# guimoOpen_PCB.net
KiCad netlist of a schematic drawn in EAGLE
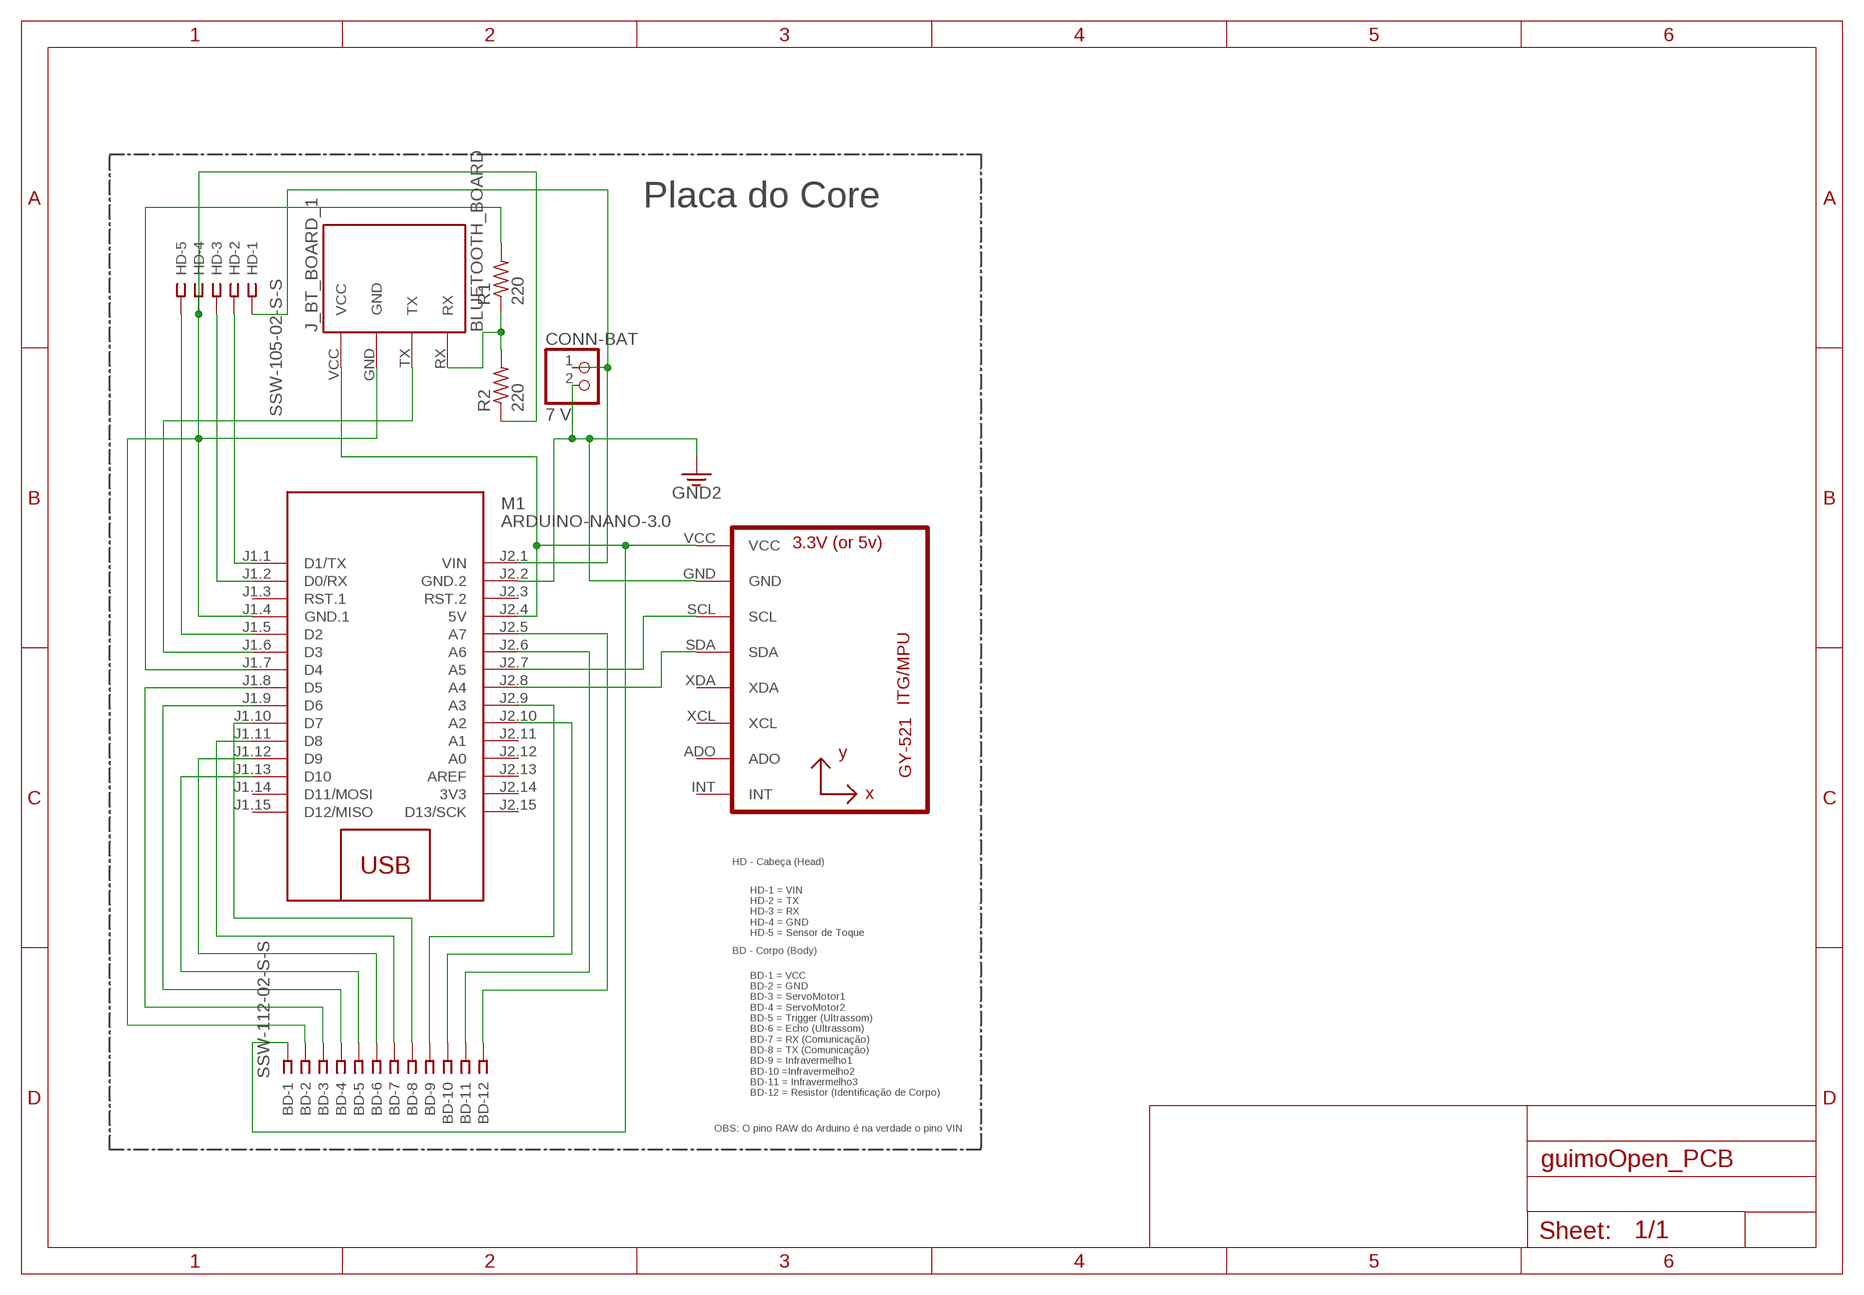
[diagram p0: schematic, sheet 1]

(export (version "E")
  (design (tool "Eeschema 10.0.6"))
  (components
    (comp (ref "BD")
      (value "SSW-112-02-S-S")
      (footprint "eagle-import:SSW-112-02-S-S")
      (libsource (lib "eagle-import") (part "SSW-112-02-S-S"))
    )
    (comp (ref "CONN-BAT")
      (value "7 V")
      (footprint "eagle-import:1X02")
      (libsource (lib "eagle-import") (part "PINHD-1X2"))
    )
    (comp (ref "HD")
      (value "SSW-105-02-S-S")
      (footprint "eagle-import:SSW-105-02-S-S")
      (libsource (lib "eagle-import") (part "SSW-105-02-S-S"))
    )
    (comp (ref "J_BT_BOARD_1")
      (value "BLUETOOTH_BOARD")
      (footprint "eagle-import:BT_BOARD_FOOTPRINT")
      (libsource (lib "eagle-import") (part "BLUETOOTH_BOARD"))
    )
    (comp (ref "M1")
      (value "ARDUINO-NANO-3.0")
      (footprint "eagle-import:ARDUINO-NANO-3.0")
      (libsource (lib "eagle-import") (part "ARDUINO-NANO-3.0"))
    )
    (comp (ref "R1")
      (value "220")
      (footprint "eagle-import:0207_7")
      (libsource (lib "eagle-import") (part "R-US_0207/7"))
    )
    (comp (ref "R2")
      (value "220")
      (footprint "eagle-import:0207_7")
      (libsource (lib "eagle-import") (part "R-US_0207/7"))
    )
    (comp (ref "U1")
      (value "GY-521MPU6050")
      (footprint "eagle-import:GY-521")
      (libsource (lib "eagle-import") (part "GY-521MPU6050"))
    )
  )
  (nets
    (net (code "1") (name "/3V3") (class "Default")
      (node (ref "M1") (pin "J2.14") (pinfunction "3V3_J2.14") (pintype "power_in"))
    )
    (net (code "2") (name "GND2") (class "Default")
      (node (ref "CONN-BAT") (pin "2") (pinfunction "2_2") (pintype "passive"))
      (node (ref "M1") (pin "J2.2") (pinfunction "GND.2_J2.2") (pintype "power_in"))
      (node (ref "U1") (pin "GND") (pinfunction "GND_GND") (pintype "bidirectional"))
    )
    (net (code "3") (name "Net-(BDB-1)") (class "Default")
      (node (ref "BD") (pin "10") (pinfunction "1_10") (pintype "passive"))
      (node (ref "M1") (pin "J2.10") (pinfunction "A2_J2.10") (pintype "bidirectional"))
    )
    (net (code "4") (name "Net-(BDC-1)") (class "Default")
      (node (ref "BD") (pin "11") (pinfunction "1_11") (pintype "passive"))
      (node (ref "M1") (pin "J2.6") (pinfunction "A6_J2.6") (pintype "bidirectional"))
    )
    (net (code "5") (name "Net-(BDD-1)") (class "Default")
      (node (ref "BD") (pin "12") (pinfunction "1_12") (pintype "passive"))
      (node (ref "M1") (pin "J2.5") (pinfunction "A7_J2.5") (pintype "bidirectional"))
    )
    (net (code "6") (name "Net-(BDE-1)") (class "Default")
      (node (ref "BD") (pin "2") (pinfunction "1_2") (pintype "passive"))
      (node (ref "HD") (pin "4") (pinfunction "1_4") (pintype "passive"))
      (node (ref "J_BT_BOARD_1") (pin "GND") (pinfunction "GND_GND") (pintype "bidirectional"))
      (node (ref "M1") (pin "J1.4") (pinfunction "GND.1_J1.4") (pintype "power_in"))
      (node (ref "R2") (pin "1") (pinfunction "1_1") (pintype "passive"))
    )
    (net (code "7") (name "Net-(BDF-1)") (class "Default")
      (node (ref "BD") (pin "3") (pinfunction "1_3") (pintype "passive"))
      (node (ref "M1") (pin "J1.8") (pinfunction "D5_J1.8") (pintype "bidirectional"))
    )
    (net (code "8") (name "Net-(BDG-1)") (class "Default")
      (node (ref "BD") (pin "4") (pinfunction "1_4") (pintype "passive"))
      (node (ref "M1") (pin "J1.9") (pinfunction "D6_J1.9") (pintype "bidirectional"))
    )
    (net (code "9") (name "Net-(BDH-1)") (class "Default")
      (node (ref "BD") (pin "5") (pinfunction "1_5") (pintype "passive"))
      (node (ref "M1") (pin "J1.13") (pinfunction "D10_J1.13") (pintype "bidirectional"))
    )
    (net (code "10") (name "Net-(BDI-1)") (class "Default")
      (node (ref "BD") (pin "6") (pinfunction "1_6") (pintype "passive"))
      (node (ref "M1") (pin "J1.12") (pinfunction "D9_J1.12") (pintype "bidirectional"))
    )
    (net (code "11") (name "Net-(BDJ-1)") (class "Default")
      (node (ref "BD") (pin "7") (pinfunction "1_7") (pintype "passive"))
      (node (ref "M1") (pin "J1.11") (pinfunction "D8_J1.11") (pintype "bidirectional"))
    )
    (net (code "12") (name "Net-(BDK-1)") (class "Default")
      (node (ref "BD") (pin "8") (pinfunction "1_8") (pintype "passive"))
      (node (ref "M1") (pin "J1.10") (pinfunction "D7_J1.10") (pintype "bidirectional"))
    )
    (net (code "13") (name "Net-(BDL-1)") (class "Default")
      (node (ref "BD") (pin "9") (pinfunction "1_9") (pintype "passive"))
      (node (ref "M1") (pin "J2.9") (pinfunction "A3_J2.9") (pintype "bidirectional"))
    )
    (net (code "14") (name "Net-(HDB-1)") (class "Default")
      (node (ref "HD") (pin "2") (pinfunction "1_2") (pintype "passive"))
      (node (ref "M1") (pin "J1.1") (pinfunction "D1/TX_J1.1") (pintype "bidirectional"))
    )
    (net (code "15") (name "Net-(HDC-1)") (class "Default")
      (node (ref "HD") (pin "3") (pinfunction "1_3") (pintype "passive"))
      (node (ref "M1") (pin "J1.2") (pinfunction "D0/RX_J1.2") (pintype "bidirectional"))
    )
    (net (code "16") (name "Net-(HDE-1)") (class "Default")
      (node (ref "HD") (pin "5") (pinfunction "1_5") (pintype "passive"))
      (node (ref "M1") (pin "J1.5") (pinfunction "D2_J1.5") (pintype "bidirectional"))
    )
    (net (code "17") (name "Net-(J_BT_BOARD_1-PadRX)") (class "Default")
      (node (ref "J_BT_BOARD_1") (pin "RX") (pinfunction "RX_RX") (pintype "bidirectional"))
      (node (ref "R1") (pin "1") (pinfunction "1_1") (pintype "passive"))
      (node (ref "R2") (pin "2") (pinfunction "2_2") (pintype "passive"))
    )
    (net (code "18") (name "Net-(M1-5V)") (class "Default")
      (node (ref "BD") (pin "1") (pinfunction "1_1") (pintype "passive"))
      (node (ref "J_BT_BOARD_1") (pin "VCC") (pinfunction "VCC_VCC") (pintype "bidirectional"))
      (node (ref "M1") (pin "J2.4") (pinfunction "5V_J2.4") (pintype "power_in"))
      (node (ref "U1") (pin "VCC") (pinfunction "VCC_VCC") (pintype "bidirectional"))
    )
    (net (code "19") (name "Net-(M1-A4)") (class "Default")
      (node (ref "M1") (pin "J2.8") (pinfunction "A4_J2.8") (pintype "bidirectional"))
      (node (ref "U1") (pin "SDA") (pinfunction "SDA_SDA") (pintype "bidirectional"))
    )
    (net (code "20") (name "Net-(M1-A5)") (class "Default")
      (node (ref "M1") (pin "J2.7") (pinfunction "A5_J2.7") (pintype "bidirectional"))
      (node (ref "U1") (pin "SCL") (pinfunction "SCL_SCL") (pintype "bidirectional"))
    )
    (net (code "21") (name "Net-(M1-D3)") (class "Default")
      (node (ref "J_BT_BOARD_1") (pin "TX") (pinfunction "TX_TX") (pintype "bidirectional"))
      (node (ref "M1") (pin "J1.6") (pinfunction "D3_J1.6") (pintype "bidirectional"))
    )
    (net (code "22") (name "Net-(M1-D4)") (class "Default")
      (node (ref "M1") (pin "J1.7") (pinfunction "D4_J1.7") (pintype "bidirectional"))
      (node (ref "R1") (pin "2") (pinfunction "2_2") (pintype "passive"))
    )
    (net (code "23") (name "Net-(M1-VIN)") (class "Default")
      (node (ref "CONN-BAT") (pin "1") (pinfunction "1_1") (pintype "passive"))
      (node (ref "HD") (pin "1") (pinfunction "1_1") (pintype "passive"))
      (node (ref "M1") (pin "J2.1") (pinfunction "VIN_J2.1") (pintype "power_in"))
    )
    (net (code "24") (name "unconnected-(M1-A0-PadJ2.12)") (class "Default")
      (node (ref "M1") (pin "J2.12") (pinfunction "A0_J2.12") (pintype "bidirectional"))
    )
    (net (code "25") (name "unconnected-(M1-A1-PadJ2.11)") (class "Default")
      (node (ref "M1") (pin "J2.11") (pinfunction "A1_J2.11") (pintype "bidirectional"))
    )
    (net (code "26") (name "unconnected-(M1-AREF-PadJ2.13)") (class "Default")
      (node (ref "M1") (pin "J2.13") (pinfunction "AREF_J2.13") (pintype "bidirectional"))
    )
    (net (code "27") (name "unconnected-(M1-D11{slash}MOSI-PadJ1.14)") (class "Default")
      (node (ref "M1") (pin "J1.14") (pinfunction "D11/MOSI_J1.14") (pintype "bidirectional"))
    )
    (net (code "28") (name "unconnected-(M1-D12{slash}MISO-PadJ1.15)") (class "Default")
      (node (ref "M1") (pin "J1.15") (pinfunction "D12/MISO_J1.15") (pintype "bidirectional"))
    )
    (net (code "29") (name "unconnected-(M1-D13{slash}SCK-PadJ2.15)") (class "Default")
      (node (ref "M1") (pin "J2.15") (pinfunction "D13/SCK_J2.15") (pintype "bidirectional"))
    )
    (net (code "30") (name "unconnected-(M1-RST.1-PadJ1.3)") (class "Default")
      (node (ref "M1") (pin "J1.3") (pinfunction "RST.1_J1.3") (pintype "bidirectional"))
    )
    (net (code "31") (name "unconnected-(M1-RST.2-PadJ2.3)") (class "Default")
      (node (ref "M1") (pin "J2.3") (pinfunction "RST.2_J2.3") (pintype "bidirectional"))
    )
    (net (code "32") (name "unconnected-(U1-PadADO)") (class "Default")
      (node (ref "U1") (pin "ADO") (pinfunction "ADO_ADO") (pintype "bidirectional"))
    )
    (net (code "33") (name "unconnected-(U1-PadINT)") (class "Default")
      (node (ref "U1") (pin "INT") (pinfunction "INT_INT") (pintype "bidirectional"))
    )
    (net (code "34") (name "unconnected-(U1-PadXCL)") (class "Default")
      (node (ref "U1") (pin "XCL") (pinfunction "XCL_XCL") (pintype "bidirectional"))
    )
    (net (code "35") (name "unconnected-(U1-PadXDA)") (class "Default")
      (node (ref "U1") (pin "XDA") (pinfunction "XDA_XDA") (pintype "bidirectional"))
    )
  )
)
